# CAN.net
KiCad netlist of a schematic drawn in Altium Designer
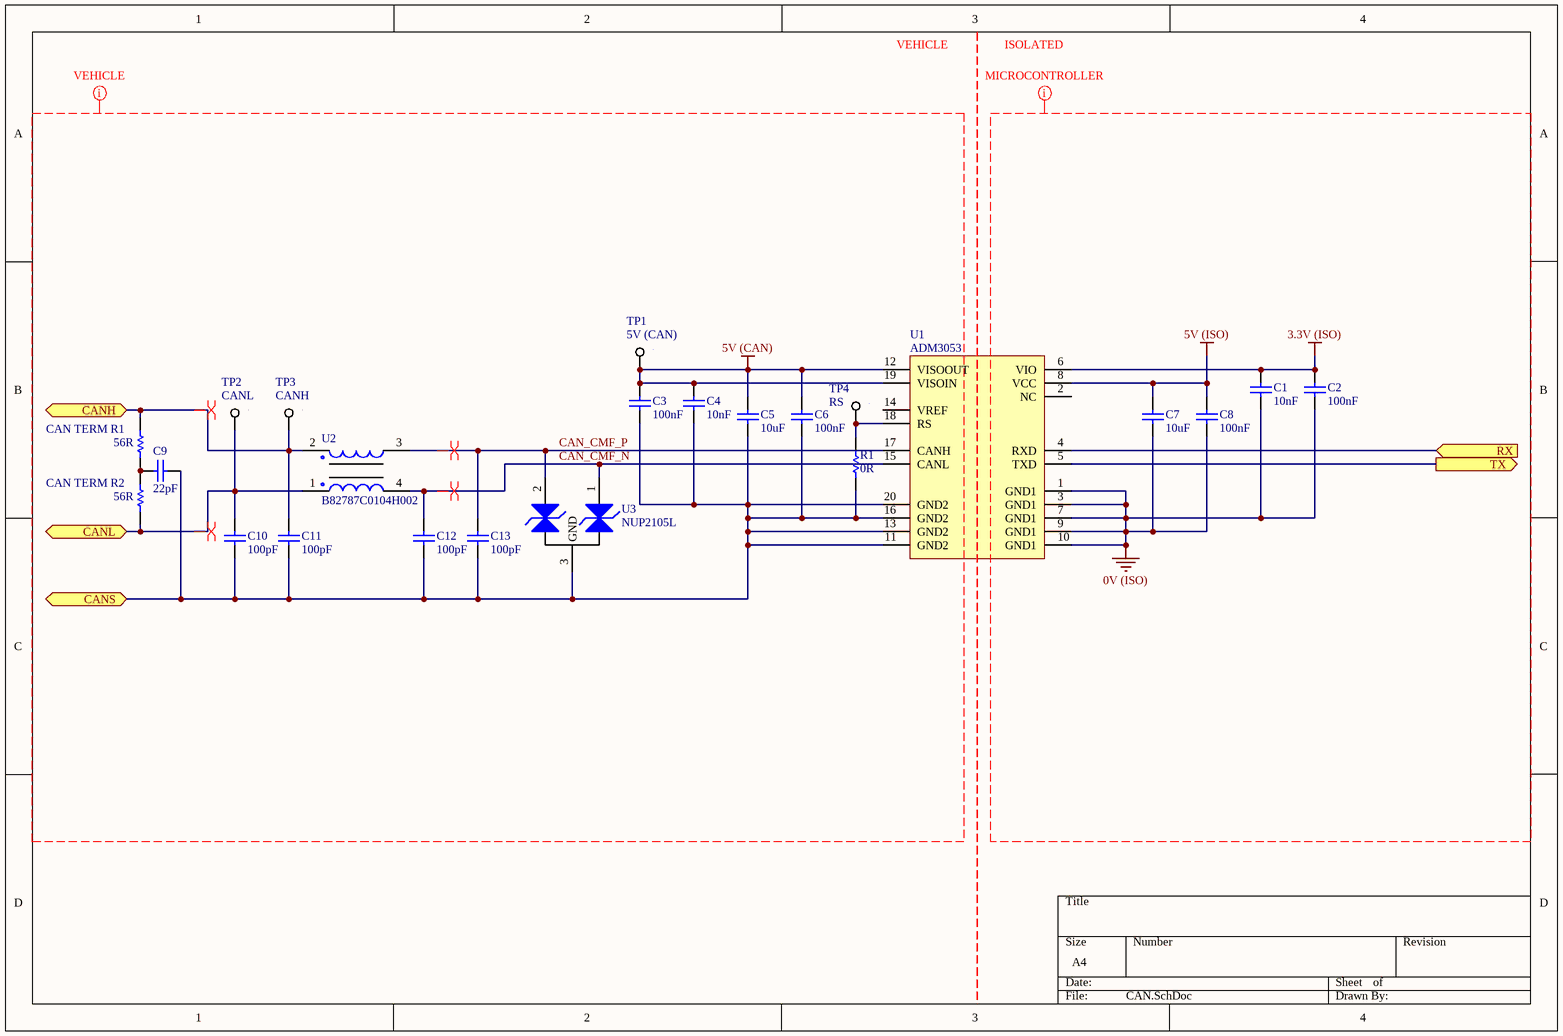
[diagram p0: CAN.SchDoc]

(export (version "E")
  (design (tool "Eeschema 10.0.6"))
  (components
    (comp (ref "C1")
      (value "10nF")
      (footprint "1206")
      (fields
        (field (name "PART NUMBER") "GCM3195C2A103JA16D")
        (field (name "TOLERANCE") "5%")
        (field (name "MANUFACTURER") "muRata")
      )
      (libsource (lib "ts_20-standard-library") (part "Capacitor"))
    )
    (comp (ref "C2")
      (value "100nF")
      (footprint "0805")
      (fields
        (field (name "PART NUMBER") "GCM21BR71H104KA37L")
        (field (name "TOLERANCE") "±10%")
        (field (name "MANUFACTURER") "muRata")
      )
      (libsource (lib "ts_20-standard-library") (part "Capacitor"))
    )
    (comp (ref "C3")
      (value "100nF")
      (footprint "0805")
      (fields
        (field (name "PART NUMBER") "GCM21BR71H104KA37L")
        (field (name "TOLERANCE") "±10%")
        (field (name "MANUFACTURER") "muRata")
      )
      (libsource (lib "ts_20-standard-library") (part "Capacitor"))
    )
    (comp (ref "C4")
      (value "10nF")
      (footprint "1206")
      (fields
        (field (name "PART NUMBER") "GCM3195C2A103JA16D")
        (field (name "TOLERANCE") "5%")
        (field (name "MANUFACTURER") "muRata")
      )
      (libsource (lib "ts_20-standard-library") (part "Capacitor"))
    )
    (comp (ref "C5")
      (value "10uF")
      (footprint "0805")
      (fields
        (field (name "PART NUMBER") "GRM21BR6YA106KE43L")
        (field (name "TOLERANCE") "10%")
        (field (name "MANUFACTURER") "muRata")
      )
      (libsource (lib "ts_20-standard-library") (part "Capacitor"))
    )
    (comp (ref "C6")
      (value "100nF")
      (footprint "0805")
      (fields
        (field (name "PART NUMBER") "GCM21BR71H104KA37L")
        (field (name "TOLERANCE") "±10%")
        (field (name "MANUFACTURER") "muRata")
      )
      (libsource (lib "ts_20-standard-library") (part "Capacitor"))
    )
    (comp (ref "C7")
      (value "10uF")
      (footprint "0805")
      (fields
        (field (name "PART NUMBER") "GRM21BR6YA106KE43L")
        (field (name "TOLERANCE") "10%")
        (field (name "MANUFACTURER") "muRata")
      )
      (libsource (lib "ts_20-standard-library") (part "Capacitor"))
    )
    (comp (ref "C8")
      (value "100nF")
      (footprint "0805")
      (fields
        (field (name "PART NUMBER") "GCM21BR71H104KA37L")
        (field (name "TOLERANCE") "±10%")
        (field (name "MANUFACTURER") "muRata")
      )
      (libsource (lib "ts_20-standard-library") (part "Capacitor"))
    )
    (comp (ref "C9")
      (value "22pF")
      (footprint "0805")
      (fields
        (field (name "PART NUMBER") "GRM21A5C2E220JW01D")
        (field (name "TOLERANCE") "±5%")
        (field (name "MANUFACTURER") "muRata")
      )
      (libsource (lib "ts_20-standard-library") (part "Capacitor"))
    )
    (comp (ref "C10")
      (value "100pF")
      (footprint "0805")
      (fields
        (field (name "PART NUMBER") "GCM2165C1H101JA16D")
        (field (name "TOLERANCE") "±5%")
        (field (name "MANUFACTURER") "muRata")
      )
      (libsource (lib "ts_20-standard-library") (part "Capacitor"))
    )
    (comp (ref "C11")
      (value "100pF")
      (footprint "0805")
      (fields
        (field (name "PART NUMBER") "GCM2165C1H101JA16D")
        (field (name "TOLERANCE") "±5%")
        (field (name "MANUFACTURER") "muRata")
      )
      (libsource (lib "ts_20-standard-library") (part "Capacitor"))
    )
    (comp (ref "C12")
      (value "100pF")
      (footprint "0805")
      (fields
        (field (name "PART NUMBER") "GCM2165C1H101JA16D")
        (field (name "TOLERANCE") "±5%")
        (field (name "MANUFACTURER") "muRata")
      )
      (libsource (lib "ts_20-standard-library") (part "Capacitor"))
    )
    (comp (ref "C13")
      (value "100pF")
      (footprint "0805")
      (fields
        (field (name "PART NUMBER") "GCM2165C1H101JA16D")
        (field (name "TOLERANCE") "±5%")
        (field (name "MANUFACTURER") "muRata")
      )
      (libsource (lib "ts_20-standard-library") (part "Capacitor"))
    )
    (comp (ref "CAN TERM R1")
      (value "56R")
      (footprint "0805")
      (fields
        (field (name "PART NUMBER") "RC0805FR0756RL")
        (field (name "MANUFACTURER") "YAGEO")
        (field (name "TOLERANCE") "0.01")
      )
      (libsource (lib "ts_20-standard-library") (part "Resistor"))
    )
    (comp (ref "CAN TERM R2")
      (value "56R")
      (footprint "0805")
      (fields
        (field (name "PART NUMBER") "RC0805FR0756RL")
        (field (name "MANUFACTURER") "YAGEO")
        (field (name "TOLERANCE") "0.01")
      )
      (libsource (lib "ts_20-standard-library") (part "Resistor"))
    )
    (comp (ref "R1")
      (value "0R")
      (footprint "0805")
      (fields
        (field (name "PART NUMBER") "RC0805FR070RL")
        (field (name "MANUFACTURER") "YAGEO")
        (field (name "TOLERANCE") "0.01")
      )
      (libsource (lib "ts_20-standard-library") (part "Resistor"))
    )
    (comp (ref "TP1")
      (value "5V (CAN)")
      (footprint "SMD Test Point 1mm")
      (fields (field (name "PART NUMBER") "SMD Test Point Small") (field (name "CONTACT") "NA"))
      (libsource (lib "ts_20-standard-connectors") (part "Test Point Small"))
    )
    (comp (ref "TP2")
      (value "CANL")
      (footprint "SMD Test Point 1mm")
      (fields (field (name "PART NUMBER") "SMD Test Point Small") (field (name "CONTACT") "NA"))
      (libsource (lib "ts_20-standard-connectors") (part "Test Point Small"))
    )
    (comp (ref "TP3")
      (value "CANH")
      (footprint "SMD Test Point 1mm")
      (fields (field (name "PART NUMBER") "SMD Test Point Small") (field (name "CONTACT") "NA"))
      (libsource (lib "ts_20-standard-connectors") (part "Test Point Small"))
    )
    (comp (ref "TP4")
      (value "RS")
      (footprint "SMD Test Point 1mm")
      (fields (field (name "PART NUMBER") "SMD Test Point Small") (field (name "CONTACT") "NA"))
      (libsource (lib "ts_20-standard-connectors") (part "Test Point Small"))
    )
    (comp (ref "U1")
      (value "ADM3053")
      (footprint "AD SOIC-W 20")
      (description "Isolated CAN Transceiver")
      (fields
        (field (name "MANUFACTURER") "Analogue Devices")
        (field (name "DIGIKEY PART NUMBER") "ADM3053BRWZ-ND")
      )
      (libsource (lib "ts_20-standard-library") (part "ADM3053"))
    )
    (comp (ref "U2")
      (value "B82787C0104H002")
      (footprint "TDK 4-PC Pad")
      (description "100µH @ 100kHz 2 Line Common Mode Choke Surface Mount 5.8 kOhms @ 10MHz 150mA DCR 2Ohm")
      (fields
        (field (name "MANUFACTURER") "EPCOS (TDK)")
        (field (name "DIGIKEY PART NUMBER") "495-4598-1-ND")
      )
      (libsource (lib "ts_20-standard-library") (part "B82787C0104H002"))
    )
    (comp (ref "U3")
      (value "NUP2105L")
      (footprint "ON SOT-23")
      (description "Dual Line CAN Bus Protector")
      (fields
        (field (name "MANUFACTURER") "ON Semiconductor")
        (field (name "DIGIKEY PART NUMBER") "NUP2105LT1GOSCT-ND")
      )
      (libsource (lib "ts_20-standard-library") (part "NUP2105L"))
    )
  )
  (nets
    (net (code "1") (name "/CANH") (class "Default")
      (node (ref "C11") (pin "2") (pinfunction "2_2") (pintype "passive"))
      (node (ref "CAN TERM R1") (pin "2") (pinfunction "2_2") (pintype "passive"))
      (node (ref "TP3") (pin "1") (pinfunction "1_1") (pintype "passive"))
      (node (ref "U2") (pin "2") (pinfunction "2_2") (pintype "passive"))
    )
    (net (code "2") (name "/CANL") (class "Default")
      (node (ref "C10") (pin "2") (pinfunction "2_2") (pintype "passive"))
      (node (ref "CAN TERM R2") (pin "1") (pinfunction "1_1") (pintype "passive"))
      (node (ref "TP2") (pin "1") (pinfunction "1_1") (pintype "passive"))
      (node (ref "U2") (pin "1") (pinfunction "1_1") (pintype "passive"))
    )
    (net (code "3") (name "/CANS") (class "Default")
      (node (ref "C10") (pin "1") (pinfunction "1_1") (pintype "passive"))
      (node (ref "C11") (pin "1") (pinfunction "1_1") (pintype "passive"))
      (node (ref "C12") (pin "1") (pinfunction "1_1") (pintype "passive"))
      (node (ref "C13") (pin "1") (pinfunction "1_1") (pintype "passive"))
      (node (ref "C3") (pin "1") (pinfunction "1_1") (pintype "passive"))
      (node (ref "C4") (pin "1") (pinfunction "1_1") (pintype "passive"))
      (node (ref "C5") (pin "1") (pinfunction "1_1") (pintype "passive"))
      (node (ref "C6") (pin "1") (pinfunction "1_1") (pintype "passive"))
      (node (ref "C9") (pin "1") (pinfunction "1_1") (pintype "passive"))
      (node (ref "R1") (pin "1") (pinfunction "1_1") (pintype "passive"))
      (node (ref "U1") (pin "11") (pinfunction "GND2_11") (pintype "passive"))
      (node (ref "U1") (pin "13") (pinfunction "GND2_13") (pintype "passive"))
      (node (ref "U1") (pin "16") (pinfunction "GND2_16") (pintype "passive"))
      (node (ref "U1") (pin "20") (pinfunction "GND2_20") (pintype "passive"))
      (node (ref "U3") (pin "3") (pinfunction "GND_3") (pintype "power_in"))
    )
    (net (code "4") (name "/CAN_CMF_N") (class "Default")
      (node (ref "C12") (pin "2") (pinfunction "2_2") (pintype "passive"))
      (node (ref "U1") (pin "15") (pinfunction "CANL_15") (pintype "passive"))
      (node (ref "U2") (pin "4") (pinfunction "4_4") (pintype "passive"))
      (node (ref "U3") (pin "1") (pinfunction "CAN_H_1") (pintype "passive"))
    )
    (net (code "5") (name "/CAN_CMF_P") (class "Default")
      (node (ref "C13") (pin "2") (pinfunction "2_2") (pintype "passive"))
      (node (ref "U1") (pin "17") (pinfunction "CANH_17") (pintype "passive"))
      (node (ref "U2") (pin "3") (pinfunction "3_3") (pintype "power_in"))
      (node (ref "U3") (pin "2") (pinfunction "CAN_L_2") (pintype "passive"))
    )
    (net (code "6") (name "/RX") (class "Default")
      (node (ref "U1") (pin "4") (pinfunction "RXD_4") (pintype "passive"))
    )
    (net (code "7") (name "/TX") (class "Default")
      (node (ref "U1") (pin "5") (pinfunction "TXD_5") (pintype "passive"))
    )
    (net (code "8") (name "0V (ISO)") (class "Default")
      (node (ref "C1") (pin "1") (pinfunction "1_1") (pintype "passive"))
      (node (ref "C2") (pin "1") (pinfunction "1_1") (pintype "passive"))
      (node (ref "C7") (pin "1") (pinfunction "1_1") (pintype "passive"))
      (node (ref "C8") (pin "1") (pinfunction "1_1") (pintype "passive"))
      (node (ref "U1") (pin "1") (pinfunction "GND1_1") (pintype "passive"))
      (node (ref "U1") (pin "10") (pinfunction "GND1_10") (pintype "passive"))
      (node (ref "U1") (pin "3") (pinfunction "GND1_3") (pintype "passive"))
      (node (ref "U1") (pin "7") (pinfunction "GND1_7") (pintype "passive"))
      (node (ref "U1") (pin "9") (pinfunction "GND1_9") (pintype "passive"))
    )
    (net (code "9") (name "3.3V (ISO)") (class "Default")
      (node (ref "C1") (pin "2") (pinfunction "2_2") (pintype "passive"))
      (node (ref "C2") (pin "2") (pinfunction "2_2") (pintype "passive"))
      (node (ref "U1") (pin "6") (pinfunction "VIO_6") (pintype "passive"))
    )
    (net (code "10") (name "5V (CAN)") (class "Default")
      (node (ref "C3") (pin "2") (pinfunction "2_2") (pintype "passive"))
      (node (ref "C4") (pin "2") (pinfunction "2_2") (pintype "passive"))
      (node (ref "C5") (pin "2") (pinfunction "2_2") (pintype "passive"))
      (node (ref "C6") (pin "2") (pinfunction "2_2") (pintype "passive"))
      (node (ref "TP1") (pin "1") (pinfunction "1_1") (pintype "passive"))
      (node (ref "U1") (pin "12") (pinfunction "VISOOUT_12") (pintype "passive"))
      (node (ref "U1") (pin "19") (pinfunction "VISOIN_19") (pintype "passive"))
    )
    (net (code "11") (name "5V (ISO)") (class "Default")
      (node (ref "C7") (pin "2") (pinfunction "2_2") (pintype "passive"))
      (node (ref "C8") (pin "2") (pinfunction "2_2") (pintype "passive"))
      (node (ref "U1") (pin "8") (pinfunction "VCC_8") (pintype "passive"))
    )
    (net (code "12") (name "Net-(C9-Pad2)") (class "Default")
      (node (ref "C9") (pin "2") (pinfunction "2_2") (pintype "passive"))
      (node (ref "CAN TERM R1") (pin "1") (pinfunction "1_1") (pintype "passive"))
      (node (ref "CAN TERM R2") (pin "2") (pinfunction "2_2") (pintype "passive"))
    )
    (net (code "13") (name "Net-(U1-RS)") (class "Default")
      (node (ref "R1") (pin "2") (pinfunction "2_2") (pintype "passive"))
      (node (ref "TP4") (pin "1") (pinfunction "1_1") (pintype "passive"))
      (node (ref "U1") (pin "18") (pinfunction "RS_18") (pintype "passive"))
    )
    (net (code "14") (name "unconnected-(U1-NC-Pad2)") (class "Default")
      (node (ref "U1") (pin "2") (pinfunction "NC_2") (pintype "passive"))
    )
    (net (code "15") (name "unconnected-(U1-VREF-Pad14)") (class "Default")
      (node (ref "U1") (pin "14") (pinfunction "VREF_14") (pintype "passive"))
    )
  )
)
